# MARLIN.net
KiCad netlist of a schematic drawn in Altium Designer
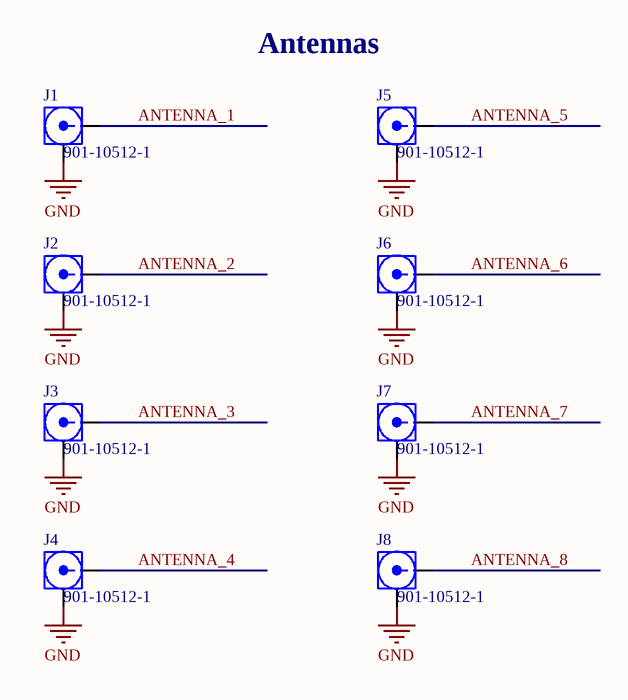
[diagram p0: MARLIN.SchDoc]

(export (version "E")
  (design (tool "Eeschema 10.0.6"))
  (components
    (comp (ref "J1")
      (value "901-10512-1")
      (footprint "901-10512-1")
      (description "RF / Coaxial Connector, SMA Coaxial, Straight Flanged Jack, Solder, 50 ohm, Beryllium Copper")
      (fields (field (name "MANUFACTURER") "Amphenol"))
      (libsource (lib "Titan") (part "901-10512-1"))
    )
    (comp (ref "J2")
      (value "901-10512-1")
      (footprint "901-10512-1")
      (description "RF / Coaxial Connector, SMA Coaxial, Straight Flanged Jack, Solder, 50 ohm, Beryllium Copper")
      (fields (field (name "MANUFACTURER") "Amphenol"))
      (libsource (lib "Titan") (part "901-10512-1"))
    )
    (comp (ref "J3")
      (value "901-10512-1")
      (footprint "901-10512-1")
      (description "RF / Coaxial Connector, SMA Coaxial, Straight Flanged Jack, Solder, 50 ohm, Beryllium Copper")
      (fields (field (name "MANUFACTURER") "Amphenol"))
      (libsource (lib "Titan") (part "901-10512-1"))
    )
    (comp (ref "J4")
      (value "901-10512-1")
      (footprint "901-10512-1")
      (description "RF / Coaxial Connector, SMA Coaxial, Straight Flanged Jack, Solder, 50 ohm, Beryllium Copper")
      (fields (field (name "MANUFACTURER") "Amphenol"))
      (libsource (lib "Titan") (part "901-10512-1"))
    )
    (comp (ref "J5")
      (value "901-10512-1")
      (footprint "901-10512-1")
      (description "RF / Coaxial Connector, SMA Coaxial, Straight Flanged Jack, Solder, 50 ohm, Beryllium Copper")
      (fields (field (name "MANUFACTURER") "Amphenol"))
      (libsource (lib "Titan") (part "901-10512-1"))
    )
    (comp (ref "J6")
      (value "901-10512-1")
      (footprint "901-10512-1")
      (description "RF / Coaxial Connector, SMA Coaxial, Straight Flanged Jack, Solder, 50 ohm, Beryllium Copper")
      (fields (field (name "MANUFACTURER") "Amphenol"))
      (libsource (lib "Titan") (part "901-10512-1"))
    )
    (comp (ref "J7")
      (value "901-10512-1")
      (footprint "901-10512-1")
      (description "RF / Coaxial Connector, SMA Coaxial, Straight Flanged Jack, Solder, 50 ohm, Beryllium Copper")
      (fields (field (name "MANUFACTURER") "Amphenol"))
      (libsource (lib "Titan") (part "901-10512-1"))
    )
    (comp (ref "J8")
      (value "901-10512-1")
      (footprint "901-10512-1")
      (description "RF / Coaxial Connector, SMA Coaxial, Straight Flanged Jack, Solder, 50 ohm, Beryllium Copper")
      (fields (field (name "MANUFACTURER") "Amphenol"))
      (libsource (lib "Titan") (part "901-10512-1"))
    )
  )
  (nets
    (net (code "1") (name "/ANTENNA_1") (class "Default") (node (ref "J1") (pin "1") (pintype "passive")))
    (net (code "2") (name "/ANTENNA_2") (class "Default") (node (ref "J2") (pin "1") (pintype "passive")))
    (net (code "3") (name "/ANTENNA_3") (class "Default") (node (ref "J3") (pin "1") (pintype "passive")))
    (net (code "4") (name "/ANTENNA_4") (class "Default") (node (ref "J4") (pin "1") (pintype "passive")))
    (net (code "5") (name "/ANTENNA_5") (class "Default") (node (ref "J5") (pin "1") (pintype "passive")))
    (net (code "6") (name "/ANTENNA_6") (class "Default") (node (ref "J6") (pin "1") (pintype "passive")))
    (net (code "7") (name "/ANTENNA_7") (class "Default") (node (ref "J7") (pin "1") (pintype "passive")))
    (net (code "8") (name "/ANTENNA_8") (class "Default") (node (ref "J8") (pin "1") (pintype "passive")))
    (net (code "9") (name "GND") (class "Default")
      (node (ref "J1") (pin "2") (pintype "passive"))
      (node (ref "J2") (pin "2") (pintype "passive"))
      (node (ref "J3") (pin "2") (pintype "passive"))
      (node (ref "J4") (pin "2") (pintype "passive"))
      (node (ref "J5") (pin "2") (pintype "passive"))
      (node (ref "J6") (pin "2") (pintype "passive"))
      (node (ref "J7") (pin "2") (pintype "passive"))
      (node (ref "J8") (pin "2") (pintype "passive"))
    )
  )
)
